# radio_rpi.net
KiCad netlist of a schematic drawn in EAGLE
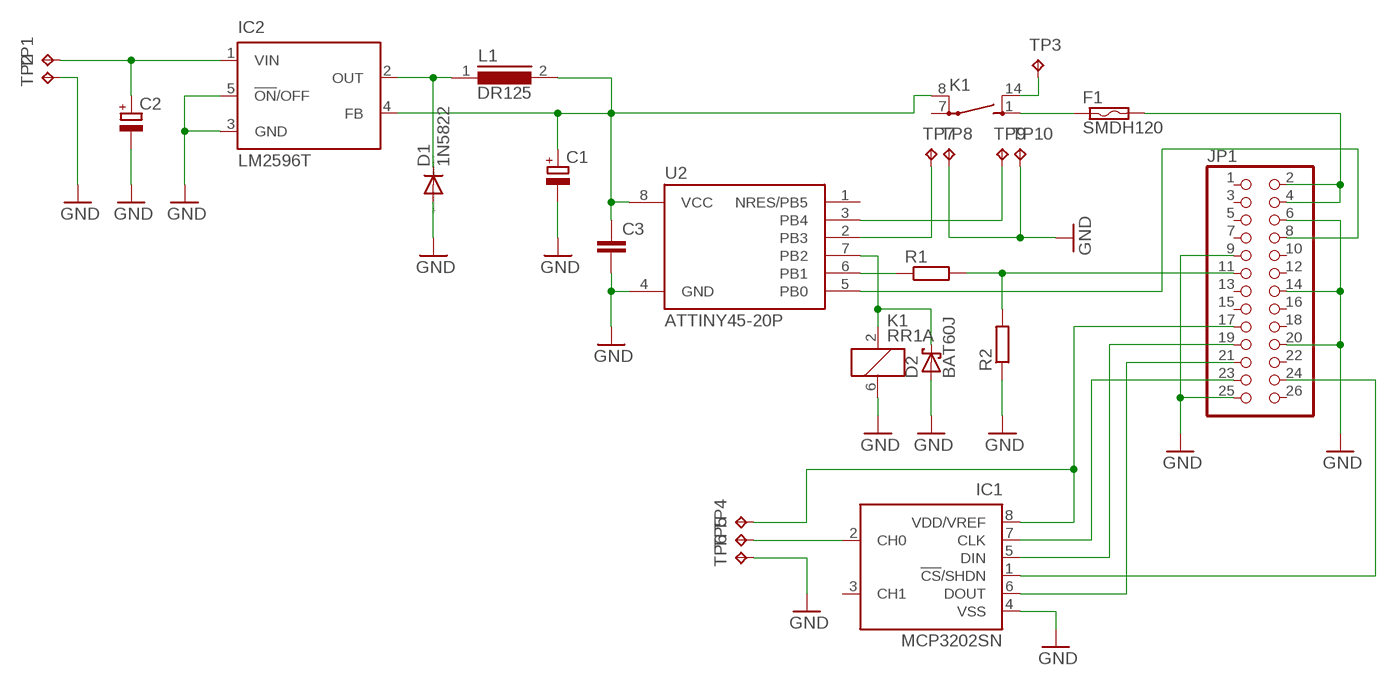
[diagram p0: schematic, sheet 1]

(export (version "E")
  (design (tool "Eeschema 10.0.6"))
  (components
    (comp (ref "C1")
      (value "CPOL-EUUD-6,3X7,7")
      (footprint "eagle-import:UD-6,3X7,7_NICHICON")
      (libsource (lib "eagle-import") (part "CPOL-EUUD-6,3X7,7"))
    )
    (comp (ref "C2")
      (value "CPOL-EUUD-10X10")
      (footprint "eagle-import:UD-10X10_NICHICON")
      (libsource (lib "eagle-import") (part "CPOL-EUUD-10X10"))
    )
    (comp (ref "C3")
      (value "C-EUC1206K")
      (footprint "eagle-import:C1206K")
      (libsource (lib "eagle-import") (part "C-EUC1206K"))
    )
    (comp (ref "D1")
      (value "1N5822")
      (footprint "eagle-import:DO201-15")
      (libsource (lib "eagle-import") (part "1N5624"))
    )
    (comp (ref "D2")
      (value "BAT60J")
      (footprint "eagle-import:SOD323_ST")
      (libsource (lib "eagle-import") (part "BAT60J"))
    )
    (comp (ref "F1")
      (value "SMDH120")
      (footprint "eagle-import:SMD050F")
      (libsource (lib "eagle-import") (part "SMDH120"))
    )
    (comp (ref "IC1")
      (value "MCP3202SN")
      (footprint "eagle-import:SO-08")
      (fields (field (name "MF") "MICROCHIP") (field (name "MPN") "MCP3202-CI/SN"))
      (libsource (lib "eagle-import") (part "MCP3202SN"))
    )
    (comp (ref "IC2")
      (value "LM2596T")
      (footprint "eagle-import:T05D")
      (fields (field (name "MPN") "LM2596T-ADJ/LF02"))
      (libsource (lib "eagle-import") (part "LM2596T"))
    )
    (comp (ref "JP1")
      (value "PINHD-2X13")
      (footprint "eagle-import:2X13")
      (libsource (lib "eagle-import") (part "PINHD-2X13"))
    )
    (comp (ref "K1")
      (value "RR1A")
      (footprint "eagle-import:RR1A")
      (libsource (lib "eagle-import") (part "RR1A"))
    )
    (comp (ref "L1")
      (value "DR125")
      (footprint "eagle-import:DR125")
      (libsource (lib "eagle-import") (part "DR125"))
    )
    (comp (ref "R1")
      (value "R-EU_M1206")
      (footprint "eagle-import:M1206")
      (libsource (lib "eagle-import") (part "R-EU_M1206"))
    )
    (comp (ref "R2")
      (value "R-EU_M1206")
      (footprint "eagle-import:M1206")
      (libsource (lib "eagle-import") (part "R-EU_M1206"))
    )
    (comp (ref "TP1")
      (value "TPTP20SQ")
      (footprint "eagle-import:TP20SQ")
      (libsource (lib "eagle-import") (part "TPTP20SQ"))
    )
    (comp (ref "TP2")
      (value "TPTP20SQ")
      (footprint "eagle-import:TP20SQ")
      (libsource (lib "eagle-import") (part "TPTP20SQ"))
    )
    (comp (ref "TP3")
      (value "TPTP20SQ")
      (footprint "eagle-import:TP20SQ")
      (libsource (lib "eagle-import") (part "TPTP20SQ"))
    )
    (comp (ref "TP4")
      (value "TPTP20SQ")
      (footprint "eagle-import:TP20SQ")
      (libsource (lib "eagle-import") (part "TPTP20SQ"))
    )
    (comp (ref "TP5")
      (value "TPTP20SQ")
      (footprint "eagle-import:TP20SQ")
      (libsource (lib "eagle-import") (part "TPTP20SQ"))
    )
    (comp (ref "TP6")
      (value "TPTP20SQ")
      (footprint "eagle-import:TP20SQ")
      (libsource (lib "eagle-import") (part "TPTP20SQ"))
    )
    (comp (ref "TP7")
      (value "TPTP20SQ")
      (footprint "eagle-import:TP20SQ")
      (libsource (lib "eagle-import") (part "TPTP20SQ"))
    )
    (comp (ref "TP8")
      (value "TPTP20SQ")
      (footprint "eagle-import:TP20SQ")
      (libsource (lib "eagle-import") (part "TPTP20SQ"))
    )
    (comp (ref "TP9")
      (value "TPTP20SQ")
      (footprint "eagle-import:TP20SQ")
      (libsource (lib "eagle-import") (part "TPTP20SQ"))
    )
    (comp (ref "TP10")
      (value "TPTP20SQ")
      (footprint "eagle-import:TP20SQ")
      (libsource (lib "eagle-import") (part "TPTP20SQ"))
    )
    (comp (ref "U2")
      (value "ATTINY45-20P")
      (footprint "eagle-import:PDIP08_300MIL")
      (libsource (lib "eagle-import") (part "ATTINY45P-20"))
    )
  )
  (nets
    (net (code "1") (name "GND") (class "Default")
      (node (ref "C1") (pin "-") (pinfunction "-_-") (pintype "passive"))
      (node (ref "C2") (pin "-") (pinfunction "-_-") (pintype "passive"))
      (node (ref "C3") (pin "2") (pinfunction "2_2") (pintype "passive"))
      (node (ref "D1") (pin "A") (pinfunction "A_A") (pintype "passive"))
      (node (ref "D2") (pin "A") (pinfunction "A_A") (pintype "passive"))
      (node (ref "IC1") (pin "4") (pinfunction "VSS_4") (pintype "input"))
      (node (ref "IC2") (pin "3") (pinfunction "GND_3") (pintype "power_in"))
      (node (ref "IC2") (pin "5") (pinfunction "~{ON}/OFF_5") (pintype "input"))
      (node (ref "JP1") (pin "14") (pinfunction "14_14") (pintype "passive"))
      (node (ref "JP1") (pin "20") (pinfunction "20_20") (pintype "passive"))
      (node (ref "JP1") (pin "25") (pinfunction "25_25") (pintype "passive"))
      (node (ref "JP1") (pin "6") (pinfunction "6_6") (pintype "passive"))
      (node (ref "JP1") (pin "9") (pinfunction "9_9") (pintype "passive"))
      (node (ref "K1") (pin "6") (pinfunction "2_6") (pintype "passive"))
      (node (ref "R2") (pin "1") (pinfunction "1_1") (pintype "passive"))
      (node (ref "TP10") (pin "TP") (pinfunction "TP_TP") (pintype "input"))
      (node (ref "TP2") (pin "TP") (pinfunction "TP_TP") (pintype "input"))
      (node (ref "TP6") (pin "TP") (pinfunction "TP_TP") (pintype "input"))
      (node (ref "TP8") (pin "TP") (pinfunction "TP_TP") (pintype "input"))
      (node (ref "U2") (pin "4") (pinfunction "GND_4") (pintype "power_in"))
    )
    (net (code "2") (name "Net-(F1-Pad1)") (class "Default")
      (node (ref "F1") (pin "1") (pinfunction "1_1") (pintype "passive"))
      (node (ref "K1") (pin "1") (pinfunction "S_1") (pintype "passive"))
    )
    (net (code "3") (name "Net-(F1-Pad2)") (class "Default")
      (node (ref "F1") (pin "2") (pinfunction "2_2") (pintype "passive"))
      (node (ref "JP1") (pin "2") (pinfunction "2_2") (pintype "passive"))
      (node (ref "JP1") (pin "4") (pinfunction "4_4") (pintype "passive"))
    )
    (net (code "4") (name "Net-(IC1-CH0)") (class "Default")
      (node (ref "IC1") (pin "2") (pinfunction "CH0_2") (pintype "input"))
      (node (ref "TP5") (pin "TP") (pinfunction "TP_TP") (pintype "input"))
    )
    (net (code "5") (name "Net-(IC1-CLK)") (class "Default")
      (node (ref "IC1") (pin "7") (pinfunction "CLK_7") (pintype "input"))
      (node (ref "JP1") (pin "23") (pinfunction "23_23") (pintype "passive"))
    )
    (net (code "6") (name "Net-(IC1-DIN)") (class "Default")
      (node (ref "IC1") (pin "5") (pinfunction "DIN_5") (pintype "input"))
      (node (ref "JP1") (pin "19") (pinfunction "19_19") (pintype "passive"))
    )
    (net (code "7") (name "Net-(IC1-DOUT)") (class "Default")
      (node (ref "IC1") (pin "6") (pinfunction "DOUT_6") (pintype "input"))
      (node (ref "JP1") (pin "21") (pinfunction "21_21") (pintype "passive"))
    )
    (net (code "8") (name "Net-(IC1-VDD{slash}VREF)") (class "Default")
      (node (ref "IC1") (pin "8") (pinfunction "VDD/VREF_8") (pintype "input"))
      (node (ref "JP1") (pin "17") (pinfunction "17_17") (pintype "passive"))
      (node (ref "TP4") (pin "TP") (pinfunction "TP_TP") (pintype "input"))
    )
    (net (code "9") (name "Net-(IC1-~{CS}{slash}SHDN)") (class "Default")
      (node (ref "IC1") (pin "1") (pinfunction "~{CS}/SHDN_1") (pintype "input"))
      (node (ref "JP1") (pin "24") (pinfunction "24_24") (pintype "passive"))
    )
    (net (code "10") (name "Net-(IC2-FB)") (class "Default")
      (node (ref "C1") (pin "+") (pinfunction "+_+") (pintype "passive"))
      (node (ref "C3") (pin "1") (pinfunction "1_1") (pintype "passive"))
      (node (ref "IC2") (pin "4") (pinfunction "FB_4") (pintype "input"))
      (node (ref "K1") (pin "8") (pinfunction "P_8") (pintype "passive"))
      (node (ref "L1") (pin "2") (pinfunction "2_2") (pintype "passive"))
      (node (ref "U2") (pin "8") (pinfunction "VCC_8") (pintype "power_in"))
    )
    (net (code "11") (name "Net-(IC2-OUT)") (class "Default")
      (node (ref "D1") (pin "C") (pinfunction "C_C") (pintype "passive"))
      (node (ref "IC2") (pin "2") (pinfunction "OUT_2") (pintype "output"))
      (node (ref "L1") (pin "1") (pinfunction "1_1") (pintype "passive"))
    )
    (net (code "12") (name "Net-(IC2-VIN)") (class "Default")
      (node (ref "C2") (pin "+") (pinfunction "+_+") (pintype "passive"))
      (node (ref "IC2") (pin "1") (pinfunction "VIN_1") (pintype "input"))
      (node (ref "TP1") (pin "TP") (pinfunction "TP_TP") (pintype "input"))
    )
    (net (code "13") (name "Net-(JP1-Pad11)") (class "Default")
      (node (ref "JP1") (pin "11") (pinfunction "11_11") (pintype "passive"))
      (node (ref "R1") (pin "2") (pinfunction "2_2") (pintype "passive"))
      (node (ref "R2") (pin "2") (pinfunction "2_2") (pintype "passive"))
    )
    (net (code "14") (name "Net-(K1A-1)") (class "Default")
      (node (ref "D2") (pin "C") (pinfunction "C_C") (pintype "passive"))
      (node (ref "K1") (pin "2") (pinfunction "1_2") (pintype "passive"))
      (node (ref "U2") (pin "7") (pinfunction "PB2_7") (pintype "bidirectional"))
    )
    (net (code "15") (name "Net-(K1B-S-Pad14)") (class "Default")
      (node (ref "K1") (pin "14") (pinfunction "S_14") (pintype "passive"))
      (node (ref "TP3") (pin "TP") (pinfunction "TP_TP") (pintype "input"))
    )
    (net (code "16") (name "Net-(U2-PB0)") (class "Default")
      (node (ref "JP1") (pin "8") (pinfunction "8_8") (pintype "passive"))
      (node (ref "U2") (pin "5") (pinfunction "PB0_5") (pintype "bidirectional"))
    )
    (net (code "17") (name "Net-(U2-PB1)") (class "Default")
      (node (ref "R1") (pin "1") (pinfunction "1_1") (pintype "passive"))
      (node (ref "U2") (pin "6") (pinfunction "PB1_6") (pintype "bidirectional"))
    )
    (net (code "18") (name "Net-(U2-PB3)") (class "Default")
      (node (ref "TP7") (pin "TP") (pinfunction "TP_TP") (pintype "input"))
      (node (ref "U2") (pin "2") (pinfunction "PB3_2") (pintype "bidirectional"))
    )
    (net (code "19") (name "Net-(U2-PB4)") (class "Default")
      (node (ref "TP9") (pin "TP") (pinfunction "TP_TP") (pintype "input"))
      (node (ref "U2") (pin "3") (pinfunction "PB4_3") (pintype "bidirectional"))
    )
    (net (code "20") (name "unconnected-(IC1-CH1-Pad3)") (class "Default")
      (node (ref "IC1") (pin "3") (pinfunction "CH1_3") (pintype "input"))
    )
    (net (code "21") (name "unconnected-(JP1-Pad1)") (class "Default")
      (node (ref "JP1") (pin "1") (pinfunction "1_1") (pintype "passive"))
    )
    (net (code "22") (name "unconnected-(JP1-Pad3)") (class "Default")
      (node (ref "JP1") (pin "3") (pinfunction "3_3") (pintype "passive"))
    )
    (net (code "23") (name "unconnected-(JP1-Pad5)") (class "Default")
      (node (ref "JP1") (pin "5") (pinfunction "5_5") (pintype "passive"))
    )
    (net (code "24") (name "unconnected-(JP1-Pad7)") (class "Default")
      (node (ref "JP1") (pin "7") (pinfunction "7_7") (pintype "passive"))
    )
    (net (code "25") (name "unconnected-(JP1-Pad10)") (class "Default")
      (node (ref "JP1") (pin "10") (pinfunction "10_10") (pintype "passive"))
    )
    (net (code "26") (name "unconnected-(JP1-Pad12)") (class "Default")
      (node (ref "JP1") (pin "12") (pinfunction "12_12") (pintype "passive"))
    )
    (net (code "27") (name "unconnected-(JP1-Pad13)") (class "Default")
      (node (ref "JP1") (pin "13") (pinfunction "13_13") (pintype "passive"))
    )
    (net (code "28") (name "unconnected-(JP1-Pad15)") (class "Default")
      (node (ref "JP1") (pin "15") (pinfunction "15_15") (pintype "passive"))
    )
    (net (code "29") (name "unconnected-(JP1-Pad16)") (class "Default")
      (node (ref "JP1") (pin "16") (pinfunction "16_16") (pintype "passive"))
    )
    (net (code "30") (name "unconnected-(JP1-Pad18)") (class "Default")
      (node (ref "JP1") (pin "18") (pinfunction "18_18") (pintype "passive"))
    )
    (net (code "31") (name "unconnected-(JP1-Pad22)") (class "Default")
      (node (ref "JP1") (pin "22") (pinfunction "22_22") (pintype "passive"))
    )
    (net (code "32") (name "unconnected-(JP1-Pad26)") (class "Default")
      (node (ref "JP1") (pin "26") (pinfunction "26_26") (pintype "passive"))
    )
    (net (code "33") (name "unconnected-(K1B-P-Pad7)") (class "Default")
      (node (ref "K1") (pin "7") (pinfunction "P_7") (pintype "passive"))
    )
    (net (code "34") (name "unconnected-(U2-NRES{slash}PB5-Pad1)") (class "Default")
      (node (ref "U2") (pin "1") (pinfunction "NRES/PB5_1") (pintype "bidirectional"))
    )
  )
)
